# 1_-_MCU.net
KiCad netlist of a schematic drawn in Altium Designer
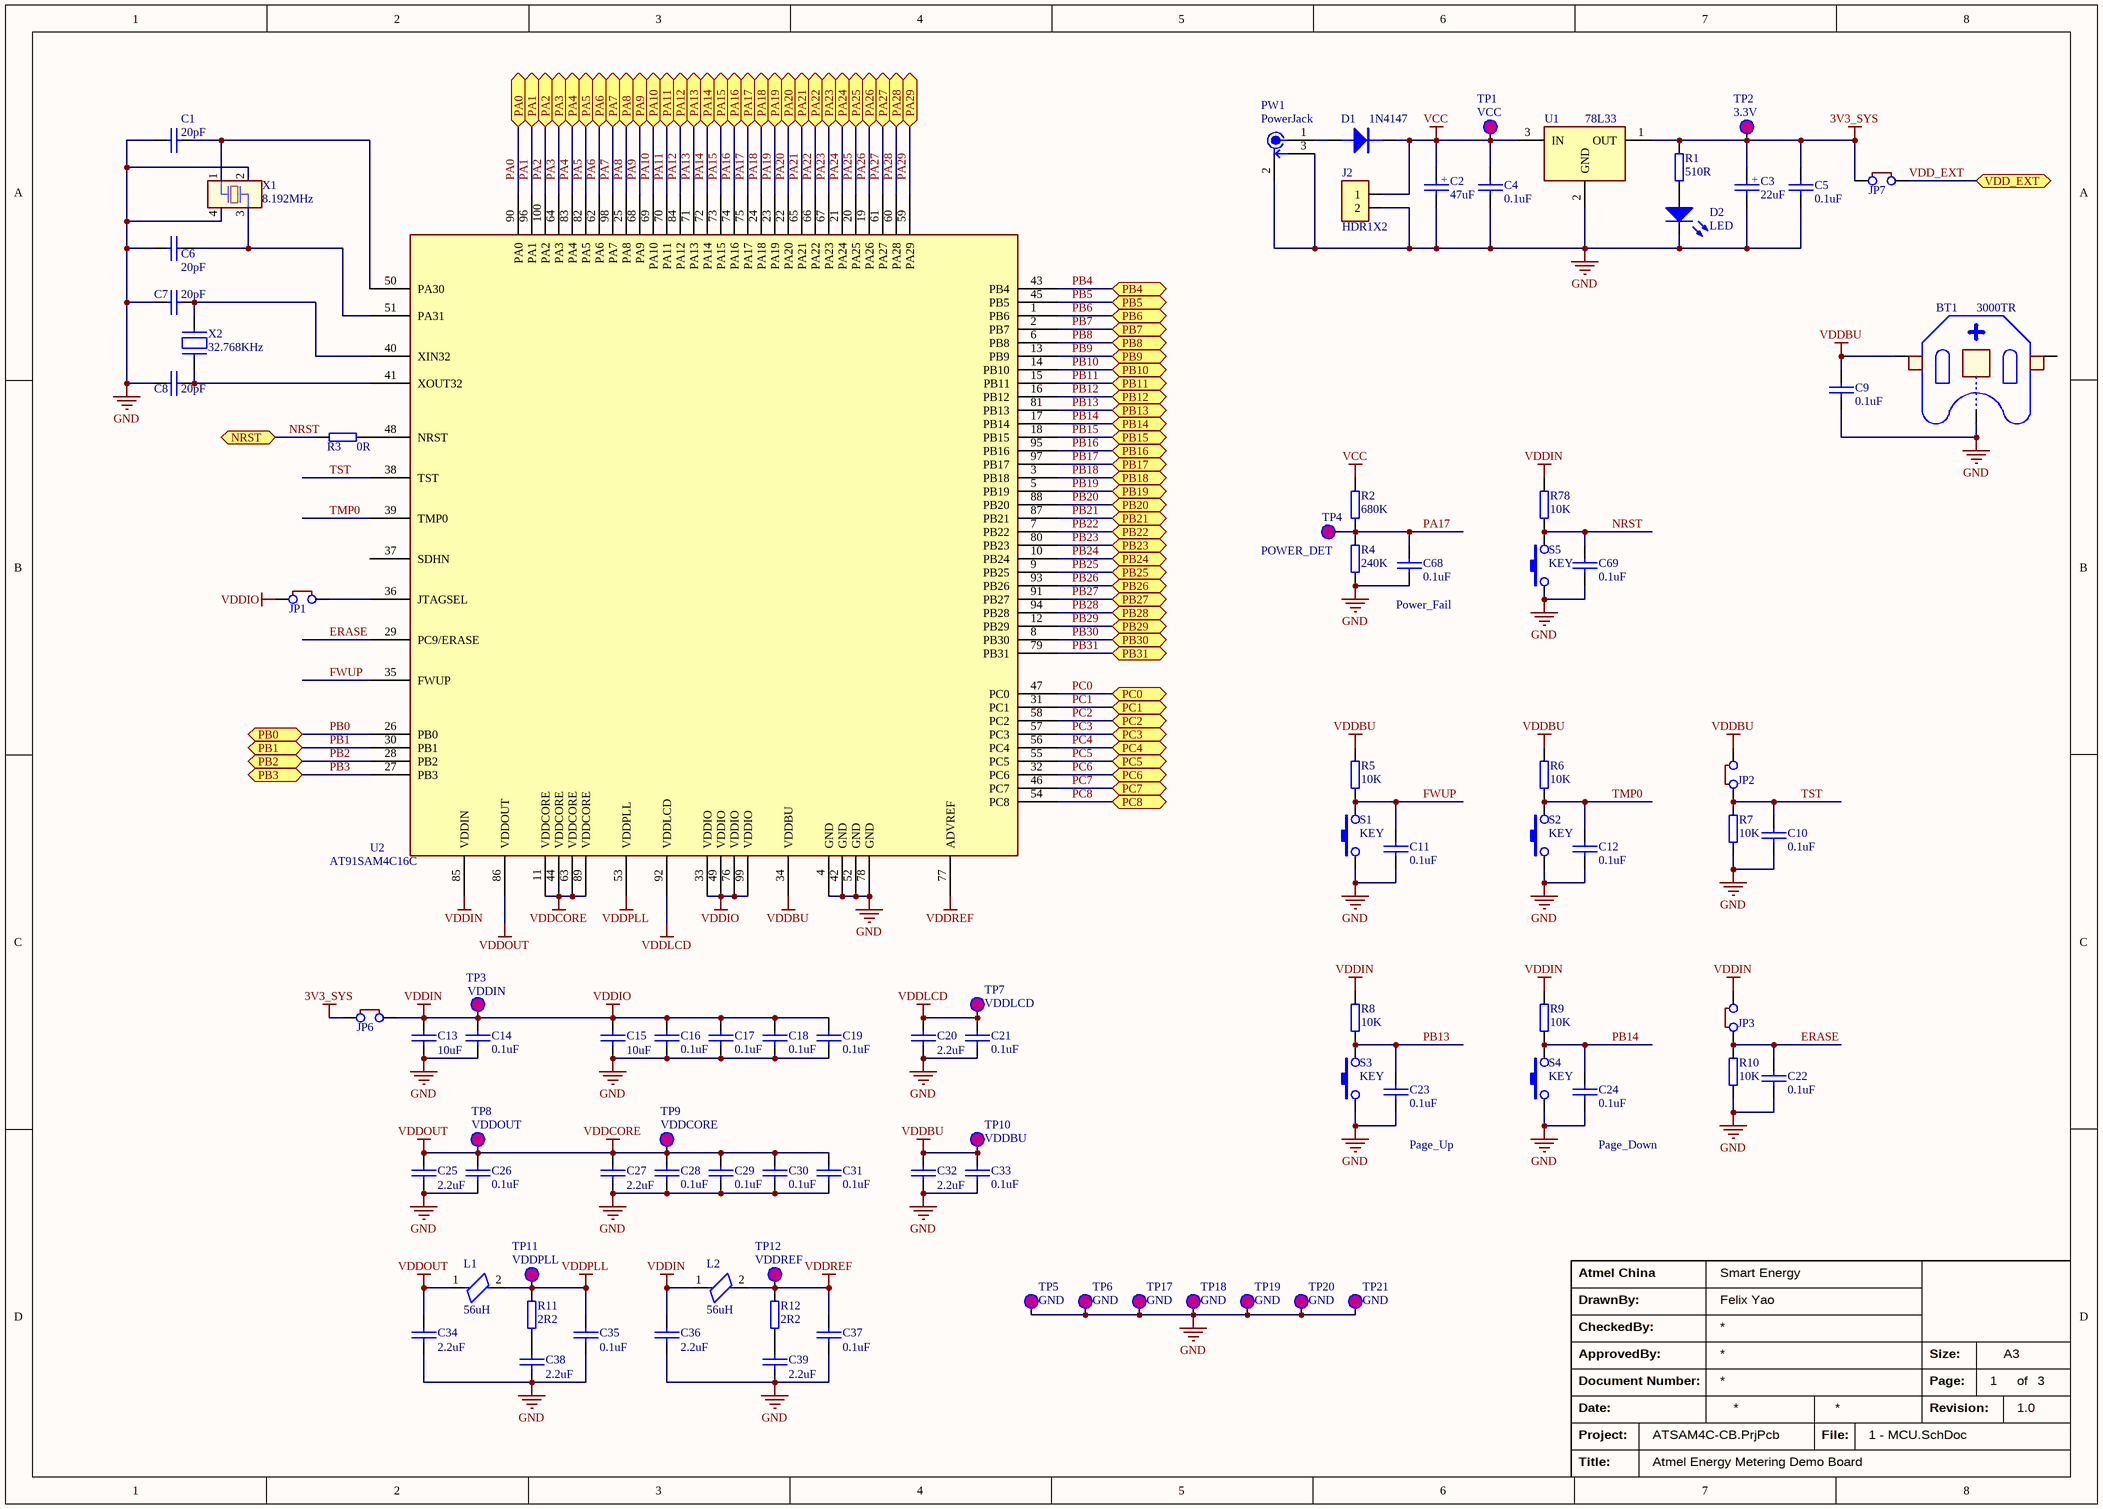
[diagram p0: 1 - MCU.SchDoc]

(export (version "E")
  (design (tool "Eeschema 10.0.6"))
  (components
    (comp (ref "BT1")
      (value "3000TR")
      (footprint "X-S_3000_01")
      (description "BATTERY HOLDER")
      (fields (field (name "MANUFACTURER") "Keystone"))
      (libsource (lib "SchLib(AD10)") (part "Battery Holder CR12_16_20_25"))
    )
    (comp (ref "C1") (value "20pF") (footprint "C0603") (libsource (lib "SchLib(AD10)") (part "CAP")))
    (comp (ref "C2")
      (value "47uF")
      (footprint "C_TANT_B3528")
      (libsource (lib "SchLib(AD10)") (part "CAP-TANT"))
    )
    (comp (ref "C3")
      (value "22uF")
      (footprint "C_TANT_B3528")
      (libsource (lib "SchLib(AD10)") (part "CAP-TANT"))
    )
    (comp (ref "C4") (value "0.1uF") (footprint "C0603") (libsource (lib "SchLib(AD10)") (part "CAP")))
    (comp (ref "C5") (value "0.1uF") (footprint "C0603") (libsource (lib "SchLib(AD10)") (part "CAP")))
    (comp (ref "C6") (value "20pF") (footprint "C0603") (libsource (lib "SchLib(AD10)") (part "CAP")))
    (comp (ref "C7") (value "20pF") (footprint "C0603") (libsource (lib "SchLib(AD10)") (part "CAP")))
    (comp (ref "C8") (value "20pF") (footprint "C0603") (libsource (lib "SchLib(AD10)") (part "CAP")))
    (comp (ref "C9") (value "0.1uF") (footprint "C0603") (libsource (lib "SchLib(AD10)") (part "CAP")))
    (comp (ref "C10") (value "0.1uF") (footprint "C0603") (libsource (lib "SchLib(AD10)") (part "CAP")))
    (comp (ref "C11") (value "0.1uF") (footprint "C0603") (libsource (lib "SchLib(AD10)") (part "CAP")))
    (comp (ref "C12") (value "0.1uF") (footprint "C0603") (libsource (lib "SchLib(AD10)") (part "CAP")))
    (comp (ref "C13") (value "10uF") (footprint "C0805") (libsource (lib "SchLib(AD10)") (part "CAP")))
    (comp (ref "C14") (value "0.1uF") (footprint "C0603") (libsource (lib "SchLib(AD10)") (part "CAP")))
    (comp (ref "C15") (value "10uF") (footprint "C0805") (libsource (lib "SchLib(AD10)") (part "CAP")))
    (comp (ref "C16") (value "0.1uF") (footprint "C0603") (libsource (lib "SchLib(AD10)") (part "CAP")))
    (comp (ref "C17") (value "0.1uF") (footprint "C0603") (libsource (lib "SchLib(AD10)") (part "CAP")))
    (comp (ref "C18") (value "0.1uF") (footprint "C0603") (libsource (lib "SchLib(AD10)") (part "CAP")))
    (comp (ref "C19") (value "0.1uF") (footprint "C0603") (libsource (lib "SchLib(AD10)") (part "CAP")))
    (comp (ref "C20") (value "2.2uF") (footprint "C0805") (libsource (lib "SchLib(AD10)") (part "CAP")))
    (comp (ref "C21") (value "0.1uF") (footprint "C0603") (libsource (lib "SchLib(AD10)") (part "CAP")))
    (comp (ref "C22") (value "0.1uF") (footprint "C0603") (libsource (lib "SchLib(AD10)") (part "CAP")))
    (comp (ref "C23") (value "0.1uF") (footprint "C0603") (libsource (lib "SchLib(AD10)") (part "CAP")))
    (comp (ref "C24") (value "0.1uF") (footprint "C0603") (libsource (lib "SchLib(AD10)") (part "CAP")))
    (comp (ref "C25") (value "2.2uF") (footprint "C0805") (libsource (lib "SchLib(AD10)") (part "CAP")))
    (comp (ref "C26") (value "0.1uF") (footprint "C0603") (libsource (lib "SchLib(AD10)") (part "CAP")))
    (comp (ref "C27") (value "2.2uF") (footprint "C0805") (libsource (lib "SchLib(AD10)") (part "CAP")))
    (comp (ref "C28") (value "0.1uF") (footprint "C0603") (libsource (lib "SchLib(AD10)") (part "CAP")))
    (comp (ref "C29") (value "0.1uF") (footprint "C0603") (libsource (lib "SchLib(AD10)") (part "CAP")))
    (comp (ref "C30") (value "0.1uF") (footprint "C0603") (libsource (lib "SchLib(AD10)") (part "CAP")))
    (comp (ref "C31") (value "0.1uF") (footprint "C0603") (libsource (lib "SchLib(AD10)") (part "CAP")))
    (comp (ref "C32") (value "2.2uF") (footprint "C0805") (libsource (lib "SchLib(AD10)") (part "CAP")))
    (comp (ref "C33") (value "0.1uF") (footprint "C0603") (libsource (lib "SchLib(AD10)") (part "CAP")))
    (comp (ref "C34") (value "2.2uF") (footprint "C0805") (libsource (lib "SchLib(AD10)") (part "CAP")))
    (comp (ref "C35") (value "0.1uF") (footprint "C0603") (libsource (lib "SchLib(AD10)") (part "CAP")))
    (comp (ref "C36") (value "2.2uF") (footprint "C0805") (libsource (lib "SchLib(AD10)") (part "CAP")))
    (comp (ref "C37") (value "0.1uF") (footprint "C0603") (libsource (lib "SchLib(AD10)") (part "CAP")))
    (comp (ref "C38") (value "2.2uF") (footprint "C0805") (libsource (lib "SchLib(AD10)") (part "CAP")))
    (comp (ref "C39") (value "2.2uF") (footprint "C0805") (libsource (lib "SchLib(AD10)") (part "CAP")))
    (comp (ref "C68") (value "0.1uF") (footprint "C0603") (libsource (lib "SchLib(AD10)") (part "CAP")))
    (comp (ref "C69") (value "0.1uF") (footprint "C0603") (libsource (lib "SchLib(AD10)") (part "CAP")))
    (comp (ref "D1") (value "1N4147") (footprint "DIODE-SMD") (libsource (lib "SchLib(AD10)") (part "DIODE")))
    (comp (ref "D2") (value "LED") (footprint "LED-0805") (libsource (lib "SchLib(AD10)") (part "LED")))
    (comp (ref "J2")
      (value "HDR1X2")
      (footprint "HDR1X2(None)")
      (libsource (lib "SchLib(AD10)") (part "HDR1X2"))
    )
    (comp (ref "JP1") (value "JMP") (footprint "JMP") (libsource (lib "SchLib(AD10)") (part "JMP")))
    (comp (ref "JP2") (value "JMP") (footprint "JMP") (libsource (lib "SchLib(AD10)") (part "JMP")))
    (comp (ref "JP3") (value "JMP") (footprint "JMP") (libsource (lib "SchLib(AD10)") (part "JMP")))
    (comp (ref "JP6") (value "JMP") (footprint "JMP") (libsource (lib "SchLib(AD10)") (part "JMP")))
    (comp (ref "JP7") (value "JMP") (footprint "JMP") (libsource (lib "SchLib(AD10)") (part "JMP")))
    (comp (ref "L1")
      (value "56uH")
      (footprint "1210")
      (description "Ferrite Bead,470OHM@100MHz,+/-25%,  200mA,")
      (fields
        (field (name "MANUFACTURER") "Murata")
        (field (name "MANUFACTURER PART NUMBER") "BLM21BD471SN1")
      )
      (libsource (lib "SchLib(AD10)") (part "BEAD_ FERRITE"))
    )
    (comp (ref "L2")
      (value "56uH")
      (footprint "1210")
      (description "Ferrite Bead,470OHM@100MHz,+/-25%,  200mA,")
      (fields
        (field (name "MANUFACTURER") "Murata")
        (field (name "MANUFACTURER PART NUMBER") "BLM21BD471SN1")
      )
      (libsource (lib "SchLib(AD10)") (part "BEAD_ FERRITE"))
    )
    (comp (ref "PW1")
      (value "PowerJack")
      (footprint "PowerJacket2.5")
      (libsource (lib "SchLib(AD10)") (part "PowerJack"))
    )
    (comp (ref "R1") (value "510R") (footprint "R0603") (libsource (lib "SchLib(AD10)") (part "RES")))
    (comp (ref "R2") (value "680K") (footprint "R0603") (libsource (lib "SchLib(AD10)") (part "RES")))
    (comp (ref "R3") (value "0R") (footprint "R0603") (libsource (lib "SchLib(AD10)") (part "RES")))
    (comp (ref "R4") (value "240K") (footprint "R0603") (libsource (lib "SchLib(AD10)") (part "RES")))
    (comp (ref "R5") (value "10K") (footprint "R0603") (libsource (lib "SchLib(AD10)") (part "RES")))
    (comp (ref "R6") (value "10K") (footprint "R0603") (libsource (lib "SchLib(AD10)") (part "RES")))
    (comp (ref "R7") (value "10K") (footprint "R0603") (libsource (lib "SchLib(AD10)") (part "RES")))
    (comp (ref "R8") (value "10K") (footprint "R0603") (libsource (lib "SchLib(AD10)") (part "RES")))
    (comp (ref "R9") (value "10K") (footprint "R0603") (libsource (lib "SchLib(AD10)") (part "RES")))
    (comp (ref "R10") (value "10K") (footprint "R0603") (libsource (lib "SchLib(AD10)") (part "RES")))
    (comp (ref "R11") (value "2R2") (footprint "R0603") (libsource (lib "SchLib(AD10)") (part "RES")))
    (comp (ref "R12") (value "2R2") (footprint "R0603") (libsource (lib "SchLib(AD10)") (part "RES")))
    (comp (ref "R78") (value "10K") (footprint "R0603") (libsource (lib "SchLib(AD10)") (part "RES")))
    (comp (ref "S1") (value "KEY") (footprint "KEY-4P - SMD") (libsource (lib "SchLib(AD10)") (part "KEY")))
    (comp (ref "S2") (value "KEY") (footprint "KEY-4P - SMD") (libsource (lib "SchLib(AD10)") (part "KEY")))
    (comp (ref "S3") (value "KEY") (footprint "KEY-4P - SMD") (libsource (lib "SchLib(AD10)") (part "KEY")))
    (comp (ref "S4") (value "KEY") (footprint "KEY-4P - SMD") (libsource (lib "SchLib(AD10)") (part "KEY")))
    (comp (ref "S5") (value "KEY") (footprint "KEY-4P - SMD") (libsource (lib "SchLib(AD10)") (part "KEY")))
    (comp (ref "TP1") (value "VCC") (footprint "TP") (libsource (lib "SchLib(AD10)") (part "TEST-POINT")))
    (comp (ref "TP2") (value "3.3V") (footprint "TP") (libsource (lib "SchLib(AD10)") (part "TEST-POINT")))
    (comp (ref "TP3") (value "VDDIN") (footprint "TP") (libsource (lib "SchLib(AD10)") (part "TEST-POINT")))
    (comp (ref "TP4")
      (value "POWER_DET")
      (footprint "TP")
      (libsource (lib "SchLib(AD10)") (part "TEST-POINT"))
    )
    (comp (ref "TP5") (value "GND") (footprint "TP") (libsource (lib "SchLib(AD10)") (part "TEST-POINT")))
    (comp (ref "TP6") (value "GND") (footprint "TP") (libsource (lib "SchLib(AD10)") (part "TEST-POINT")))
    (comp (ref "TP7") (value "VDDLCD") (footprint "TP") (libsource (lib "SchLib(AD10)") (part "TEST-POINT")))
    (comp (ref "TP8") (value "VDDOUT") (footprint "TP") (libsource (lib "SchLib(AD10)") (part "TEST-POINT")))
    (comp (ref "TP9") (value "VDDCORE") (footprint "TP") (libsource (lib "SchLib(AD10)") (part "TEST-POINT")))
    (comp (ref "TP10") (value "VDDBU") (footprint "TP") (libsource (lib "SchLib(AD10)") (part "TEST-POINT")))
    (comp (ref "TP11") (value "VDDPLL") (footprint "TP") (libsource (lib "SchLib(AD10)") (part "TEST-POINT")))
    (comp (ref "TP12") (value "VDDREF") (footprint "TP") (libsource (lib "SchLib(AD10)") (part "TEST-POINT")))
    (comp (ref "TP17") (value "GND") (footprint "TP") (libsource (lib "SchLib(AD10)") (part "TEST-POINT")))
    (comp (ref "TP18") (value "GND") (footprint "TP") (libsource (lib "SchLib(AD10)") (part "TEST-POINT")))
    (comp (ref "TP19") (value "GND") (footprint "TP") (libsource (lib "SchLib(AD10)") (part "TEST-POINT")))
    (comp (ref "TP20") (value "GND") (footprint "TP") (libsource (lib "SchLib(AD10)") (part "TEST-POINT")))
    (comp (ref "TP21") (value "GND") (footprint "TP") (libsource (lib "SchLib(AD10)") (part "TEST-POINT")))
    (comp (ref "U1") (value "78L33") (footprint "SOT-89") (libsource (lib "SchLib(AD10)") (part "78LXX")))
    (comp (ref "U2")
      (value "AT91SAM4C16C")
      (footprint "LQFP-100")
      (libsource (lib "SchLib(AD10)") (part "AT91SAM4C16C"))
    )
    (comp (ref "X1")
      (value "8.192MHz")
      (footprint "crystal_5032")
      (description "Crystal,ABM3B-8.192MHz-B2-T,8.192MHz,+/-20PPM,18PF")
      (fields
        (field (name "MANUFACTURER") "Abracon")
        (field (name "MANUFACTURER PART NUMBER") "ABM3B-8.192MHZ-B2-T")
      )
      (libsource (lib "SchLib(AD10)") (part "12MHz"))
    )
    (comp (ref "X2")
      (value "32.768KHz")
      (footprint "CFPX-217")
      (libsource (lib "SchLib(AD10)") (part "XTAL-T"))
    )
  )
  (nets
    (net (code "1") (name "/ERASE") (class "Default")
      (node (ref "C22") (pin "2") (pintype "passive"))
      (node (ref "JP3") (pin "1") (pinfunction "1_1") (pintype "passive"))
      (node (ref "R10") (pin "1") (pinfunction "1_1") (pintype "passive"))
      (node (ref "U2") (pin "29") (pinfunction "PC9/ERASE_29") (pintype "passive"))
    )
    (net (code "2") (name "/FWUP") (class "Default")
      (node (ref "C11") (pin "2") (pintype "passive"))
      (node (ref "R5") (pin "1") (pinfunction "1_1") (pintype "passive"))
      (node (ref "S1") (pin "2") (pinfunction "2_2") (pintype "passive"))
      (node (ref "U2") (pin "35") (pinfunction "FWUP_35") (pintype "passive"))
    )
    (net (code "3") (name "/NRST") (class "Default")
      (node (ref "C69") (pin "2") (pintype "passive"))
      (node (ref "R3") (pin "2") (pinfunction "2_2") (pintype "passive"))
      (node (ref "R78") (pin "1") (pinfunction "1_1") (pintype "passive"))
      (node (ref "S5") (pin "2") (pinfunction "2_2") (pintype "passive"))
    )
    (net (code "4") (name "/PA0") (class "Default")
      (node (ref "U2") (pin "90") (pinfunction "PA0_90") (pintype "passive"))
    )
    (net (code "5") (name "/PA1") (class "Default")
      (node (ref "U2") (pin "96") (pinfunction "PA1_96") (pintype "passive"))
    )
    (net (code "6") (name "/PA2") (class "Default")
      (node (ref "U2") (pin "100") (pinfunction "PA2_100") (pintype "passive"))
    )
    (net (code "7") (name "/PA3") (class "Default")
      (node (ref "U2") (pin "64") (pinfunction "PA3_64") (pintype "passive"))
    )
    (net (code "8") (name "/PA4") (class "Default")
      (node (ref "U2") (pin "83") (pinfunction "PA4_83") (pintype "passive"))
    )
    (net (code "9") (name "/PA5") (class "Default")
      (node (ref "U2") (pin "82") (pinfunction "PA5_82") (pintype "passive"))
    )
    (net (code "10") (name "/PA6") (class "Default")
      (node (ref "U2") (pin "62") (pinfunction "PA6_62") (pintype "passive"))
    )
    (net (code "11") (name "/PA7") (class "Default")
      (node (ref "U2") (pin "98") (pinfunction "PA7_98") (pintype "passive"))
    )
    (net (code "12") (name "/PA8") (class "Default")
      (node (ref "U2") (pin "25") (pinfunction "PA8_25") (pintype "passive"))
    )
    (net (code "13") (name "/PA9") (class "Default")
      (node (ref "U2") (pin "68") (pinfunction "PA9_68") (pintype "passive"))
    )
    (net (code "14") (name "/PA10") (class "Default")
      (node (ref "U2") (pin "69") (pinfunction "PA10_69") (pintype "passive"))
    )
    (net (code "15") (name "/PA11") (class "Default")
      (node (ref "U2") (pin "70") (pinfunction "PA11_70") (pintype "passive"))
    )
    (net (code "16") (name "/PA12") (class "Default")
      (node (ref "U2") (pin "84") (pinfunction "PA12_84") (pintype "passive"))
    )
    (net (code "17") (name "/PA13") (class "Default")
      (node (ref "U2") (pin "71") (pinfunction "PA13_71") (pintype "passive"))
    )
    (net (code "18") (name "/PA14") (class "Default")
      (node (ref "U2") (pin "72") (pinfunction "PA14_72") (pintype "passive"))
    )
    (net (code "19") (name "/PA15") (class "Default")
      (node (ref "U2") (pin "73") (pinfunction "PA15_73") (pintype "passive"))
    )
    (net (code "20") (name "/PA16") (class "Default")
      (node (ref "U2") (pin "74") (pinfunction "PA16_74") (pintype "passive"))
    )
    (net (code "21") (name "/PA17") (class "Default")
      (node (ref "C68") (pin "2") (pintype "passive"))
      (node (ref "R2") (pin "1") (pinfunction "1_1") (pintype "passive"))
      (node (ref "R4") (pin "2") (pinfunction "2_2") (pintype "passive"))
      (node (ref "TP4") (pin "1") (pinfunction "1_1") (pintype "passive"))
      (node (ref "U2") (pin "75") (pinfunction "PA17_75") (pintype "passive"))
    )
    (net (code "22") (name "/PA18") (class "Default")
      (node (ref "U2") (pin "24") (pinfunction "PA18_24") (pintype "passive"))
    )
    (net (code "23") (name "/PA19") (class "Default")
      (node (ref "U2") (pin "23") (pinfunction "PA19_23") (pintype "passive"))
    )
    (net (code "24") (name "/PA20") (class "Default")
      (node (ref "U2") (pin "22") (pinfunction "PA20_22") (pintype "passive"))
    )
    (net (code "25") (name "/PA21") (class "Default")
      (node (ref "U2") (pin "65") (pinfunction "PA21_65") (pintype "passive"))
    )
    (net (code "26") (name "/PA22") (class "Default")
      (node (ref "U2") (pin "66") (pinfunction "PA22_66") (pintype "passive"))
    )
    (net (code "27") (name "/PA23") (class "Default")
      (node (ref "U2") (pin "67") (pinfunction "PA23_67") (pintype "passive"))
    )
    (net (code "28") (name "/PA24") (class "Default")
      (node (ref "U2") (pin "21") (pinfunction "PA24_21") (pintype "passive"))
    )
    (net (code "29") (name "/PA25") (class "Default")
      (node (ref "U2") (pin "20") (pinfunction "PA25_20") (pintype "passive"))
    )
    (net (code "30") (name "/PA26") (class "Default")
      (node (ref "U2") (pin "19") (pinfunction "PA26_19") (pintype "passive"))
    )
    (net (code "31") (name "/PA27") (class "Default")
      (node (ref "U2") (pin "61") (pinfunction "PA27_61") (pintype "passive"))
    )
    (net (code "32") (name "/PA28") (class "Default")
      (node (ref "U2") (pin "60") (pinfunction "PA28_60") (pintype "passive"))
    )
    (net (code "33") (name "/PA29") (class "Default")
      (node (ref "U2") (pin "59") (pinfunction "PA29_59") (pintype "passive"))
    )
    (net (code "34") (name "/PB0") (class "Default")
      (node (ref "U2") (pin "26") (pinfunction "PB0_26") (pintype "passive"))
    )
    (net (code "35") (name "/PB1") (class "Default")
      (node (ref "U2") (pin "30") (pinfunction "PB1_30") (pintype "passive"))
    )
    (net (code "36") (name "/PB2") (class "Default")
      (node (ref "U2") (pin "28") (pinfunction "PB2_28") (pintype "passive"))
    )
    (net (code "37") (name "/PB3") (class "Default")
      (node (ref "U2") (pin "27") (pinfunction "PB3_27") (pintype "passive"))
    )
    (net (code "38") (name "/PB4") (class "Default")
      (node (ref "U2") (pin "43") (pinfunction "PB4_43") (pintype "passive"))
    )
    (net (code "39") (name "/PB5") (class "Default")
      (node (ref "U2") (pin "45") (pinfunction "PB5_45") (pintype "passive"))
    )
    (net (code "40") (name "/PB6") (class "Default")
      (node (ref "U2") (pin "1") (pinfunction "PB6_1") (pintype "passive"))
    )
    (net (code "41") (name "/PB7") (class "Default")
      (node (ref "U2") (pin "2") (pinfunction "PB7_2") (pintype "passive"))
    )
    (net (code "42") (name "/PB8") (class "Default")
      (node (ref "U2") (pin "6") (pinfunction "PB8_6") (pintype "passive"))
    )
    (net (code "43") (name "/PB9") (class "Default")
      (node (ref "U2") (pin "13") (pinfunction "PB9_13") (pintype "passive"))
    )
    (net (code "44") (name "/PB10") (class "Default")
      (node (ref "U2") (pin "14") (pinfunction "PB10_14") (pintype "passive"))
    )
    (net (code "45") (name "/PB11") (class "Default")
      (node (ref "U2") (pin "15") (pinfunction "PB11_15") (pintype "passive"))
    )
    (net (code "46") (name "/PB12") (class "Default")
      (node (ref "U2") (pin "16") (pinfunction "PB12_16") (pintype "passive"))
    )
    (net (code "47") (name "/PB13") (class "Default")
      (node (ref "C23") (pin "2") (pintype "passive"))
      (node (ref "R8") (pin "1") (pinfunction "1_1") (pintype "passive"))
      (node (ref "S3") (pin "2") (pinfunction "2_2") (pintype "passive"))
      (node (ref "U2") (pin "81") (pinfunction "PB13_81") (pintype "passive"))
    )
    (net (code "48") (name "/PB14") (class "Default")
      (node (ref "C24") (pin "2") (pintype "passive"))
      (node (ref "R9") (pin "1") (pinfunction "1_1") (pintype "passive"))
      (node (ref "S4") (pin "2") (pinfunction "2_2") (pintype "passive"))
      (node (ref "U2") (pin "17") (pinfunction "PB14_17") (pintype "passive"))
    )
    (net (code "49") (name "/PB15") (class "Default")
      (node (ref "U2") (pin "18") (pinfunction "PB15_18") (pintype "passive"))
    )
    (net (code "50") (name "/PB16") (class "Default")
      (node (ref "U2") (pin "95") (pinfunction "PB16_95") (pintype "passive"))
    )
    (net (code "51") (name "/PB17") (class "Default")
      (node (ref "U2") (pin "97") (pinfunction "PB17_97") (pintype "passive"))
    )
    (net (code "52") (name "/PB18") (class "Default")
      (node (ref "U2") (pin "3") (pinfunction "PB18_3") (pintype "passive"))
    )
    (net (code "53") (name "/PB19") (class "Default")
      (node (ref "U2") (pin "5") (pinfunction "PB19_5") (pintype "passive"))
    )
    (net (code "54") (name "/PB20") (class "Default")
      (node (ref "U2") (pin "88") (pinfunction "PB20_88") (pintype "passive"))
    )
    (net (code "55") (name "/PB21") (class "Default")
      (node (ref "U2") (pin "87") (pinfunction "PB21_87") (pintype "passive"))
    )
    (net (code "56") (name "/PB22") (class "Default")
      (node (ref "U2") (pin "7") (pinfunction "PB22_7") (pintype "passive"))
    )
    (net (code "57") (name "/PB23") (class "Default")
      (node (ref "U2") (pin "80") (pinfunction "PB23_80") (pintype "passive"))
    )
    (net (code "58") (name "/PB24") (class "Default")
      (node (ref "U2") (pin "10") (pinfunction "PB24_10") (pintype "passive"))
    )
    (net (code "59") (name "/PB25") (class "Default")
      (node (ref "U2") (pin "9") (pinfunction "PB25_9") (pintype "passive"))
    )
    (net (code "60") (name "/PB26") (class "Default")
      (node (ref "U2") (pin "93") (pinfunction "PB26_93") (pintype "passive"))
    )
    (net (code "61") (name "/PB27") (class "Default")
      (node (ref "U2") (pin "91") (pinfunction "PB27_91") (pintype "passive"))
    )
    (net (code "62") (name "/PB28") (class "Default")
      (node (ref "U2") (pin "94") (pinfunction "PB28_94") (pintype "passive"))
    )
    (net (code "63") (name "/PB29") (class "Default")
      (node (ref "U2") (pin "12") (pinfunction "PB29_12") (pintype "passive"))
    )
    (net (code "64") (name "/PB30") (class "Default")
      (node (ref "U2") (pin "8") (pinfunction "PB30_8") (pintype "passive"))
    )
    (net (code "65") (name "/PB31") (class "Default")
      (node (ref "U2") (pin "79") (pinfunction "PB31_79") (pintype "passive"))
    )
    (net (code "66") (name "/PC0") (class "Default")
      (node (ref "U2") (pin "47") (pinfunction "PC0_47") (pintype "passive"))
    )
    (net (code "67") (name "/PC1") (class "Default")
      (node (ref "U2") (pin "31") (pinfunction "PC1_31") (pintype "passive"))
    )
    (net (code "68") (name "/PC2") (class "Default")
      (node (ref "U2") (pin "58") (pinfunction "PC2_58") (pintype "passive"))
    )
    (net (code "69") (name "/PC3") (class "Default")
      (node (ref "U2") (pin "57") (pinfunction "PC3_57") (pintype "passive"))
    )
    (net (code "70") (name "/PC4") (class "Default")
      (node (ref "U2") (pin "56") (pinfunction "PC4_56") (pintype "passive"))
    )
    (net (code "71") (name "/PC5") (class "Default")
      (node (ref "U2") (pin "55") (pinfunction "PC5_55") (pintype "passive"))
    )
    (net (code "72") (name "/PC6") (class "Default")
      (node (ref "U2") (pin "32") (pinfunction "PC6_32") (pintype "passive"))
    )
    (net (code "73") (name "/PC7") (class "Default")
      (node (ref "U2") (pin "46") (pinfunction "PC7_46") (pintype "passive"))
    )
    (net (code "74") (name "/PC8") (class "Default")
      (node (ref "U2") (pin "54") (pinfunction "PC8_54") (pintype "passive"))
    )
    (net (code "75") (name "/TMP0") (class "Default")
      (node (ref "C12") (pin "2") (pintype "passive"))
      (node (ref "R6") (pin "1") (pinfunction "1_1") (pintype "passive"))
      (node (ref "S2") (pin "2") (pinfunction "2_2") (pintype "passive"))
      (node (ref "U2") (pin "39") (pinfunction "TMP0_39") (pintype "passive"))
    )
    (net (code "76") (name "/TST") (class "Default")
      (node (ref "C10") (pin "2") (pintype "passive"))
      (node (ref "JP2") (pin "1") (pinfunction "1_1") (pintype "passive"))
      (node (ref "R7") (pin "1") (pinfunction "1_1") (pintype "passive"))
      (node (ref "U2") (pin "38") (pinfunction "TST_38") (pintype "passive"))
    )
    (net (code "77") (name "/VDD_EXT") (class "Default")
      (node (ref "JP7") (pin "2") (pinfunction "2_2") (pintype "passive"))
    )
    (net (code "78") (name "3V3_SYS") (class "Default")
      (node (ref "C3") (pin "1") (pintype "passive"))
      (node (ref "C5") (pin "2") (pintype "passive"))
      (node (ref "JP6") (pin "1") (pinfunction "1_1") (pintype "passive"))
      (node (ref "JP7") (pin "1") (pinfunction "1_1") (pintype "passive"))
      (node (ref "R1") (pin "2") (pinfunction "2_2") (pintype "passive"))
      (node (ref "TP2") (pin "1") (pinfunction "1_1") (pintype "passive"))
      (node (ref "U1") (pin "1") (pinfunction "OUT_1") (pintype "passive"))
    )
    (net (code "79") (name "GND") (class "Default")
      (node (ref "BT1") (pin "1") (pinfunction "M_1") (pintype "passive"))
      (node (ref "C1") (pin "1") (pintype "passive"))
      (node (ref "C10") (pin "1") (pintype "passive"))
      (node (ref "C11") (pin "1") (pintype "passive"))
      (node (ref "C12") (pin "1") (pintype "passive"))
      (node (ref "C13") (pin "1") (pintype "passive"))
      (node (ref "C14") (pin "1") (pintype "passive"))
      (node (ref "C15") (pin "1") (pintype "passive"))
      (node (ref "C16") (pin "1") (pintype "passive"))
      (node (ref "C17") (pin "1") (pintype "passive"))
      (node (ref "C18") (pin "1") (pintype "passive"))
      (node (ref "C19") (pin "1") (pintype "passive"))
      (node (ref "C2") (pin "2") (pintype "passive"))
      (node (ref "C20") (pin "1") (pintype "passive"))
      (node (ref "C21") (pin "1") (pintype "passive"))
      (node (ref "C22") (pin "1") (pintype "passive"))
      (node (ref "C23") (pin "1") (pintype "passive"))
      (node (ref "C24") (pin "1") (pintype "passive"))
      (node (ref "C25") (pin "1") (pintype "passive"))
      (node (ref "C26") (pin "1") (pintype "passive"))
      (node (ref "C27") (pin "1") (pintype "passive"))
      (node (ref "C28") (pin "1") (pintype "passive"))
      (node (ref "C29") (pin "1") (pintype "passive"))
      (node (ref "C3") (pin "2") (pintype "passive"))
      (node (ref "C30") (pin "1") (pintype "passive"))
      (node (ref "C31") (pin "1") (pintype "passive"))
      (node (ref "C32") (pin "1") (pintype "passive"))
      (node (ref "C33") (pin "1") (pintype "passive"))
      (node (ref "C34") (pin "1") (pintype "passive"))
      (node (ref "C35") (pin "1") (pintype "passive"))
      (node (ref "C36") (pin "1") (pintype "passive"))
      (node (ref "C37") (pin "1") (pintype "passive"))
      (node (ref "C38") (pin "1") (pintype "passive"))
      (node (ref "C39") (pin "1") (pintype "passive"))
      (node (ref "C4") (pin "1") (pintype "passive"))
      (node (ref "C5") (pin "1") (pintype "passive"))
      (node (ref "C6") (pin "1") (pintype "passive"))
      (node (ref "C68") (pin "1") (pintype "passive"))
      (node (ref "C69") (pin "1") (pintype "passive"))
      (node (ref "C7") (pin "1") (pintype "passive"))
      (node (ref "C8") (pin "1") (pintype "passive"))
      (node (ref "C9") (pin "1") (pintype "passive"))
      (node (ref "D2") (pin "K") (pinfunction "K_K") (pintype "passive"))
      (node (ref "J2") (pin "2") (pinfunction "2_2") (pintype "passive"))
      (node (ref "PW1") (pin "2") (pinfunction "2_2") (pintype "passive"))
      (node (ref "PW1") (pin "3") (pinfunction "3_3") (pintype "passive"))
      (node (ref "R10") (pin "2") (pinfunction "2_2") (pintype "passive"))
      (node (ref "R4") (pin "1") (pinfunction "1_1") (pintype "passive"))
      (node (ref "R7") (pin "2") (pinfunction "2_2") (pintype "passive"))
      (node (ref "S1") (pin "1") (pinfunction "1_1") (pintype "passive"))
      (node (ref "S2") (pin "1") (pinfunction "1_1") (pintype "passive"))
      (node (ref "S3") (pin "1") (pinfunction "1_1") (pintype "passive"))
      (node (ref "S4") (pin "1") (pinfunction "1_1") (pintype "passive"))
      (node (ref "S5") (pin "1") (pinfunction "1_1") (pintype "passive"))
      (node (ref "TP17") (pin "1") (pinfunction "1_1") (pintype "passive"))
      (node (ref "TP18") (pin "1") (pinfunction "1_1") (pintype "passive"))
      (node (ref "TP19") (pin "1") (pinfunction "1_1") (pintype "passive"))
      (node (ref "TP20") (pin "1") (pinfunction "1_1") (pintype "passive"))
      (node (ref "TP21") (pin "1") (pinfunction "1_1") (pintype "passive"))
      (node (ref "TP5") (pin "1") (pinfunction "1_1") (pintype "passive"))
      (node (ref "TP6") (pin "1") (pinfunction "1_1") (pintype "passive"))
      (node (ref "U1") (pin "2") (pinfunction "GND_2") (pintype "passive"))
      (node (ref "U2") (pin "4") (pinfunction "GND_4") (pintype "passive"))
      (node (ref "U2") (pin "42") (pinfunction "GND_42") (pintype "passive"))
      (node (ref "U2") (pin "52") (pinfunction "GND_52") (pintype "passive"))
      (node (ref "U2") (pin "78") (pinfunction "GND_78") (pintype "passive"))
      (node (ref "X1") (pin "2") (pinfunction "2_2") (pintype "passive"))
      (node (ref "X1") (pin "4") (pinfunction "4_4") (pintype "passive"))
    )
    (net (code "80") (name "Net-(C38-Pad2)") (class "Default")
      (node (ref "C38") (pin "2") (pintype "passive"))
      (node (ref "R11") (pin "1") (pinfunction "1_1") (pintype "passive"))
    )
    (net (code "81") (name "Net-(C39-Pad2)") (class "Default")
      (node (ref "C39") (pin "2") (pintype "passive"))
      (node (ref "R12") (pin "1") (pinfunction "1_1") (pintype "passive"))
    )
    (net (code "82") (name "Net-(D1-PadA)") (class "Default")
      (node (ref "D1") (pin "A") (pintype "passive"))
      (node (ref "PW1") (pin "1") (pinfunction "1_1") (pintype "passive"))
    )
    (net (code "83") (name "Net-(D2-PadA)") (class "Default")
      (node (ref "D2") (pin "A") (pinfunction "A_A") (pintype "passive"))
      (node (ref "R1") (pin "1") (pinfunction "1_1") (pintype "passive"))
    )
    (net (code "84") (name "Net-(U2-JTAGSEL)") (class "Default")
      (node (ref "JP1") (pin "2") (pinfunction "2_2") (pintype "passive"))
      (node (ref "U2") (pin "36") (pinfunction "JTAGSEL_36") (pintype "passive"))
    )
    (net (code "85") (name "Net-(U2-NRST)") (class "Default")
      (node (ref "R3") (pin "1") (pinfunction "1_1") (pintype "passive"))
      (node (ref "U2") (pin "48") (pinfunction "NRST_48") (pintype "passive"))
    )
    (net (code "86") (name "Net-(U2-PA30)") (class "Default")
      (node (ref "C1") (pin "2") (pintype "passive"))
      (node (ref "U2") (pin "50") (pinfunction "PA30_50") (pintype "passive"))
      (node (ref "X1") (pin "1") (pinfunction "1_1") (pintype "passive"))
    )
    (net (code "87") (name "Net-(U2-PA31)") (class "Default")
      (node (ref "C6") (pin "2") (pintype "passive"))
      (node (ref "U2") (pin "51") (pinfunction "PA31_51") (pintype "passive"))
      (node (ref "X1") (pin "3") (pinfunction "3_3") (pintype "passive"))
    )
    (net (code "88") (name "Net-(U2-XIN32)") (class "Default")
      (node (ref "C7") (pin "2") (pintype "passive"))
      (node (ref "U2") (pin "40") (pinfunction "XIN32_40") (pintype "passive"))
      (node (ref "X2") (pin "1") (pintype "passive"))
    )
    (net (code "89") (name "Net-(U2-XOUT32)") (class "Default")
      (node (ref "C8") (pin "2") (pintype "passive"))
      (node (ref "U2") (pin "41") (pinfunction "XOUT32_41") (pintype "passive"))
      (node (ref "X2") (pin "2") (pintype "passive"))
    )
    (net (code "90") (name "VCC") (class "Default")
      (node (ref "C2") (pin "1") (pintype "passive"))
      (node (ref "C4") (pin "2") (pintype "passive"))
      (node (ref "D1") (pin "K") (pintype "passive"))
      (node (ref "J2") (pin "1") (pinfunction "1_1") (pintype "passive"))
      (node (ref "R2") (pin "2") (pinfunction "2_2") (pintype "passive"))
      (node (ref "TP1") (pin "1") (pinfunction "1_1") (pintype "passive"))
      (node (ref "U1") (pin "3") (pinfunction "IN_3") (pintype "passive"))
    )
    (net (code "91") (name "VDDBU") (class "Default")
      (node (ref "BT1") (pin "3") (pinfunction "P2_3") (pintype "passive"))
      (node (ref "C32") (pin "2") (pintype "passive"))
      (node (ref "C33") (pin "2") (pintype "passive"))
      (node (ref "C9") (pin "2") (pintype "passive"))
      (node (ref "JP2") (pin "2") (pinfunction "2_2") (pintype "passive"))
      (node (ref "R5") (pin "2") (pinfunction "2_2") (pintype "passive"))
      (node (ref "R6") (pin "2") (pinfunction "2_2") (pintype "passive"))
      (node (ref "TP10") (pin "1") (pinfunction "1_1") (pintype "passive"))
      (node (ref "U2") (pin "34") (pinfunction "VDDBU_34") (pintype "passive"))
    )
    (net (code "92") (name "VDDCORE") (class "Default")
      (node (ref "C25") (pin "2") (pintype "passive"))
      (node (ref "C26") (pin "2") (pintype "passive"))
      (node (ref "C27") (pin "2") (pintype "passive"))
      (node (ref "C28") (pin "2") (pintype "passive"))
      (node (ref "C29") (pin "2") (pintype "passive"))
      (node (ref "C30") (pin "2") (pintype "passive"))
      (node (ref "C31") (pin "2") (pintype "passive"))
      (node (ref "C34") (pin "2") (pintype "passive"))
      (node (ref "L1") (pin "1") (pinfunction "1_1") (pintype "passive"))
      (node (ref "TP8") (pin "1") (pinfunction "1_1") (pintype "passive"))
      (node (ref "TP9") (pin "1") (pinfunction "1_1") (pintype "passive"))
      (node (ref "U2") (pin "11") (pinfunction "VDDCORE_11") (pintype "passive"))
      (node (ref "U2") (pin "44") (pinfunction "VDDCORE_44") (pintype "passive"))
      (node (ref "U2") (pin "63") (pinfunction "VDDCORE_63") (pintype "passive"))
      (node (ref "U2") (pin "86") (pinfunction "VDDOUT_86") (pintype "passive"))
      (node (ref "U2") (pin "89") (pinfunction "VDDCORE_89") (pintype "passive"))
    )
    (net (code "93") (name "VDDIN") (class "Default")
      (node (ref "C13") (pin "2") (pintype "passive"))
      (node (ref "C14") (pin "2") (pintype "passive"))
      (node (ref "C15") (pin "2") (pintype "passive"))
      (node (ref "C16") (pin "2") (pintype "passive"))
      (node (ref "C17") (pin "2") (pintype "passive"))
      (node (ref "C18") (pin "2") (pintype "passive"))
      (node (ref "C19") (pin "2") (pintype "passive"))
      (node (ref "C36") (pin "2") (pintype "passive"))
      (node (ref "JP1") (pin "1") (pinfunction "1_1") (pintype "passive"))
      (node (ref "JP3") (pin "2") (pinfunction "2_2") (pintype "passive"))
      (node (ref "JP6") (pin "2") (pinfunction "2_2") (pintype "passive"))
      (node (ref "L2") (pin "1") (pinfunction "1_1") (pintype "passive"))
      (node (ref "R78") (pin "2") (pinfunction "2_2") (pintype "passive"))
      (node (ref "R8") (pin "2") (pinfunction "2_2") (pintype "passive"))
      (node (ref "R9") (pin "2") (pinfunction "2_2") (pintype "passive"))
      (node (ref "TP3") (pin "1") (pinfunction "1_1") (pintype "passive"))
      (node (ref "U2") (pin "33") (pinfunction "VDDIO_33") (pintype "passive"))
      (node (ref "U2") (pin "49") (pinfunction "VDDIO_49") (pintype "passive"))
      (node (ref "U2") (pin "76") (pinfunction "VDDIO_76") (pintype "passive"))
      (node (ref "U2") (pin "85") (pinfunction "VDDIN_85") (pintype "passive"))
      (node (ref "U2") (pin "99") (pinfunction "VDDIO_99") (pintype "passive"))
    )
    (net (code "94") (name "VDDLCD") (class "Default")
      (node (ref "C20") (pin "2") (pintype "passive"))
      (node (ref "C21") (pin "2") (pintype "passive"))
      (node (ref "TP7") (pin "1") (pinfunction "1_1") (pintype "passive"))
      (node (ref "U2") (pin "92") (pinfunction "VDDLCD_92") (pintype "passive"))
    )
    (net (code "95") (name "VDDPLL") (class "Default")
      (node (ref "C35") (pin "2") (pintype "passive"))
      (node (ref "L1") (pin "2") (pinfunction "2_2") (pintype "passive"))
      (node (ref "R11") (pin "2") (pinfunction "2_2") (pintype "passive"))
      (node (ref "TP11") (pin "1") (pinfunction "1_1") (pintype "passive"))
      (node (ref "U2") (pin "53") (pinfunction "VDDPLL_53") (pintype "passive"))
    )
    (net (code "96") (name "VDDREF") (class "Default")
      (node (ref "C37") (pin "2") (pintype "passive"))
      (node (ref "L2") (pin "2") (pinfunction "2_2") (pintype "passive"))
      (node (ref "R12") (pin "2") (pinfunction "2_2") (pintype "passive"))
      (node (ref "TP12") (pin "1") (pinfunction "1_1") (pintype "passive"))
      (node (ref "U2") (pin "77") (pinfunction "ADVREF_77") (pintype "passive"))
    )
    (net (code "97") (name "unconnected-(BT1-P1-Pad2)") (class "Default")
      (node (ref "BT1") (pin "2") (pinfunction "P1_2") (pintype "passive"))
    )
    (net (code "98") (name "unconnected-(U2-SDHN-Pad37)") (class "Default")
      (node (ref "U2") (pin "37") (pinfunction "SDHN_37") (pintype "passive"))
    )
  )
)
